# CAN.net
KiCad netlist of a schematic drawn in Altium Designer
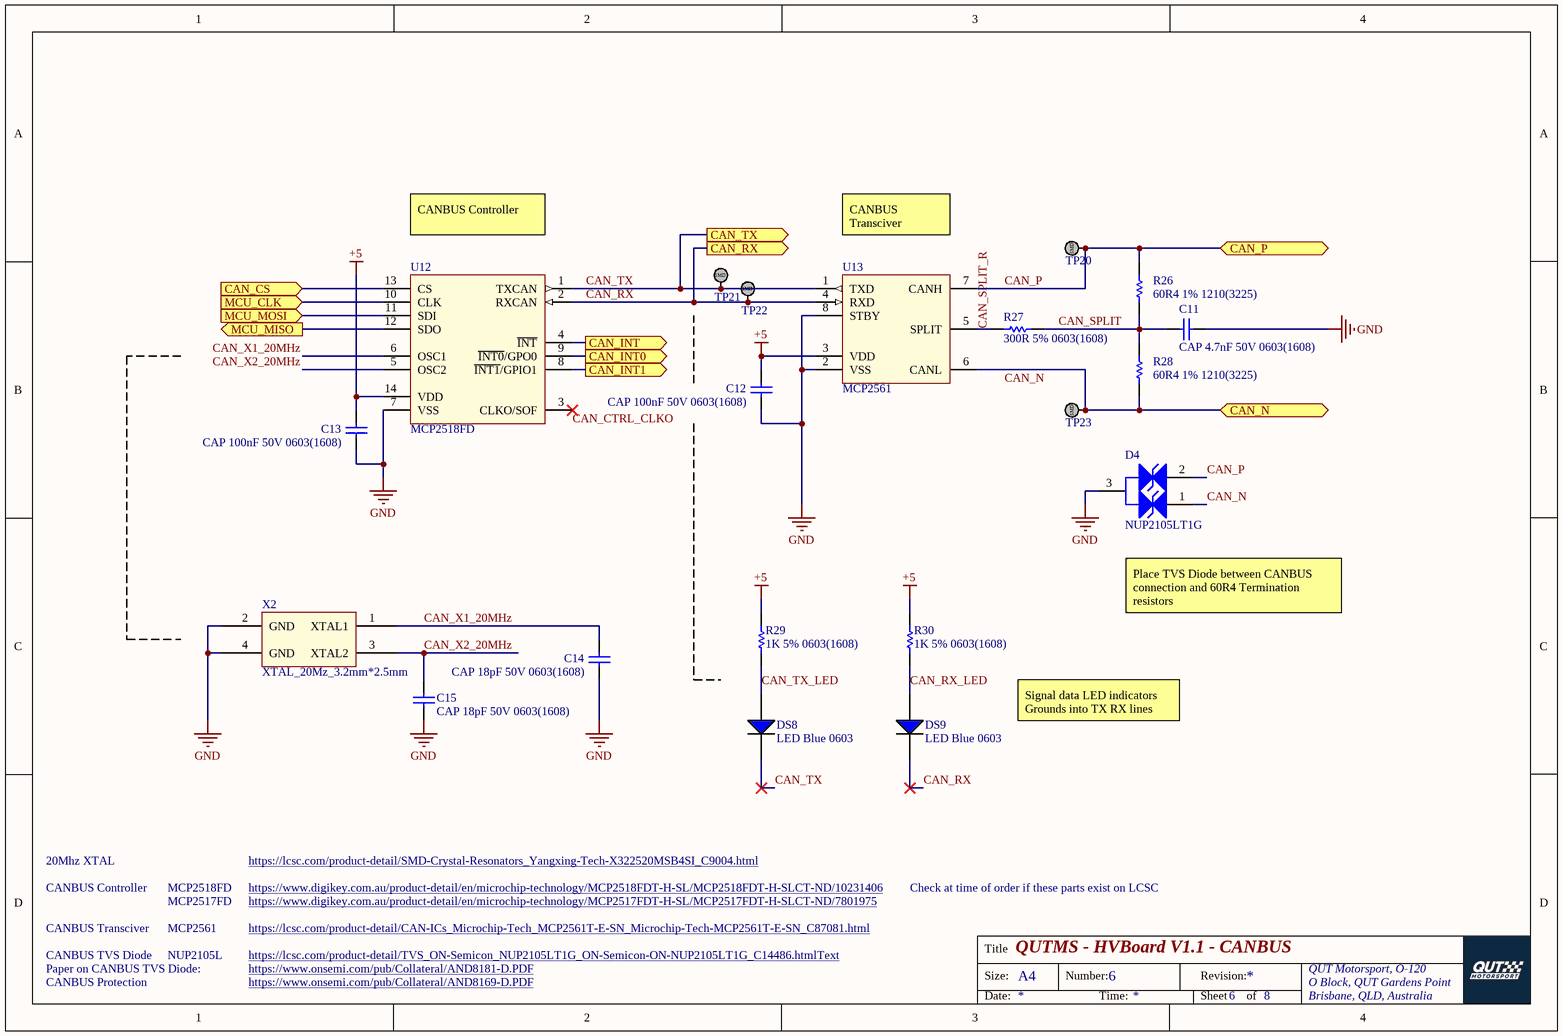
[diagram p0: CAN.SchDoc]

(export (version "E")
  (design (tool "Eeschema 10.0.6"))
  (components
    (comp (ref "C11")
      (value "CAP 4.7nF 50V 0603(1608)")
      (footprint "CAPC0603(1608)100_M")
      (description "CAP 4.7nF 50V ±5% 0603 (1608 Metric) Thickness 1mm SMD")
      (fields (field (name "TOLERANCE") "Â±5%"))
      (libsource (lib "Altium Content Vault") (part "CAP"))
    )
    (comp (ref "C12")
      (value "CAP 100nF 50V 0603(1608)")
      (footprint "CAPC0603(1608)100_L")
      (description "CAP 100nF 50V ±5% 0603 (1608 Metric) Thickness 1mm SMD")
      (fields (field (name "TOLERANCE") "Â±5%"))
      (libsource (lib "Altium Content Vault") (part "CAP"))
    )
    (comp (ref "C13")
      (value "CAP 100nF 50V 0603(1608)")
      (footprint "CAPC0603(1608)100_L")
      (description "CAP 100nF 50V ±5% 0603 (1608 Metric) Thickness 1mm SMD")
      (fields (field (name "TOLERANCE") "Â±5%"))
      (libsource (lib "Altium Content Vault") (part "CAP"))
    )
    (comp (ref "C14")
      (value "CAP 18pF 50V 0603(1608)")
      (footprint "CAPC0603(1608)100_L")
      (description "CAP 18pF 50V ±1% 0603 (1608 Metric) Thickness 1mm SMD")
      (fields (field (name "TOLERANCE") "Â±1%"))
      (libsource (lib "Altium Content Vault") (part "CAP"))
    )
    (comp (ref "C15")
      (value "CAP 18pF 50V 0603(1608)")
      (footprint "CAPC0603(1608)100_L")
      (description "CAP 18pF 50V ±1% 0603 (1608 Metric) Thickness 1mm SMD")
      (fields (field (name "TOLERANCE") "Â±1%"))
      (libsource (lib "Altium Content Vault") (part "CAP"))
    )
    (comp (ref "D4")
      (value "NUP2105LT1G")
      (footprint "ONSC-SOT-23-3-318-08_V")
      (description "Dual Line CAN Bus Protector, 3-Pin SOT-23, Pb-Free, Tape and Reel")
      (fields (field (name "MANUFACTURER") "On Semiconductor"))
      (libsource (lib "Altium Content Vault") (part "ONSC-NUP21X5X-SOT-23-3-318-08"))
    )
    (comp (ref "DS8")
      (value "LED Blue 0603")
      (footprint "LED BLUE 0603")
      (libsource (lib "QUTMS_LEDLibrary") (part "LED BLUE 0603"))
    )
    (comp (ref "DS9")
      (value "LED Blue 0603")
      (footprint "LED BLUE 0603")
      (libsource (lib "QUTMS_LEDLibrary") (part "LED BLUE 0603"))
    )
    (comp (ref "R26")
      (value "60R4 1% 1210(3225)")
      (footprint "RESC1210(3225)_L")
      (description "60R4 0.5W 1% 1210 (3225 Metric)  SMD")
      (fields (field (name "TOLERANCE") "1 %") (field (name "POWER") "0.5 W"))
      (libsource (lib "Altium Content Vault") (part "RES"))
    )
    (comp (ref "R27")
      (value "300R 5% 0603(1608)")
      (footprint "RESC0603(1608)_N")
      (description "300R 0.1W 5% 0603 (1608 Metric)  SMD")
      (fields (field (name "TOLERANCE") "5 %") (field (name "POWER") "0.1 W"))
      (libsource (lib "Altium Content Vault") (part "RES"))
    )
    (comp (ref "R28")
      (value "60R4 1% 1210(3225)")
      (footprint "RESC1210(3225)_L")
      (description "60R4 0.5W 1% 1210 (3225 Metric)  SMD")
      (fields (field (name "TOLERANCE") "1 %") (field (name "POWER") "0.5 W"))
      (libsource (lib "Altium Content Vault") (part "RES"))
    )
    (comp (ref "R29")
      (value "1K 5% 0603(1608)")
      (footprint "RESC0603(1608)_L")
      (description "1K 0.1W 5% 0603 (1608 Metric)  SMD")
      (fields (field (name "TOLERANCE") "5 %") (field (name "POWER") "0.1 W"))
      (libsource (lib "Altium Content Vault") (part "RES"))
    )
    (comp (ref "R30")
      (value "1K 5% 0603(1608)")
      (footprint "RESC0603(1608)_L")
      (description "1K 0.1W 5% 0603 (1608 Metric)  SMD")
      (fields (field (name "TOLERANCE") "5 %") (field (name "POWER") "0.1 W"))
      (libsource (lib "Altium Content Vault") (part "RES"))
    )
    (comp (ref "TP20")
      (value "TestPoint_SMD")
      (footprint "TestPointSMD")
      (libsource (lib "StandardTest") (part "TestPoint_SMD"))
    )
    (comp (ref "TP21")
      (value "TestPoint_SMD")
      (footprint "TestPointSMD")
      (libsource (lib "StandardTest") (part "TestPoint_SMD"))
    )
    (comp (ref "TP22")
      (value "TestPoint_SMD")
      (footprint "TestPointSMD")
      (libsource (lib "StandardTest") (part "TestPoint_SMD"))
    )
    (comp (ref "TP23")
      (value "TestPoint_SMD")
      (footprint "TestPointSMD")
      (libsource (lib "StandardTest") (part "TestPoint_SMD"))
    )
    (comp (ref "U12")
      (value "MCP2518FD")
      (footprint "MCP2517FD SOIC")
      (libsource (lib "QUTMS_CANLibrary") (part "MCP2518FD"))
    )
    (comp (ref "U13")
      (value "MCP2561")
      (footprint "MCP2561 SOIC")
      (libsource (lib "QUTMS_CANLibrary") (part "MCP2561"))
    )
    (comp (ref "X2")
      (value "XTAL_20Mz_3.2mm*2.5mm")
      (footprint "3.2mm*2.5mm")
      (libsource (lib "QUTMS_CrystalLibrary") (part "XTAL_20Mz_3.2mm*2.5mm"))
    )
  )
  (nets
    (net (code "1") (name "+5") (class "Default")
      (node (ref "C12") (pin "2") (pinfunction "2_2") (pintype "passive"))
      (node (ref "C13") (pin "2") (pinfunction "2_2") (pintype "passive"))
      (node (ref "R29") (pin "2") (pinfunction "2_2") (pintype "passive"))
      (node (ref "R30") (pin "2") (pinfunction "2_2") (pintype "passive"))
      (node (ref "U12") (pin "14") (pinfunction "VDD_14") (pintype "passive"))
      (node (ref "U13") (pin "3") (pinfunction "VDD_3") (pintype "passive"))
    )
    (net (code "2") (name "/CAN_CS") (class "Default")
      (node (ref "U12") (pin "13") (pinfunction "CS_13") (pintype "passive"))
    )
    (net (code "3") (name "/CAN_CTRL_CLKO") (class "Default")
      (node (ref "U12") (pin "3") (pinfunction "CLKO/SOF_3") (pintype "passive+no_connect"))
    )
    (net (code "4") (name "/CAN_INT") (class "Default")
      (node (ref "U12") (pin "4") (pinfunction "~{INT}_4") (pintype "passive"))
    )
    (net (code "5") (name "/CAN_INT0") (class "Default")
      (node (ref "U12") (pin "9") (pinfunction "~{INT0}/GPO0_9") (pintype "passive"))
    )
    (net (code "6") (name "/CAN_INT1") (class "Default")
      (node (ref "U12") (pin "8") (pinfunction "~{INT1}/GPIO1_8") (pintype "passive"))
    )
    (net (code "7") (name "/CAN_N") (class "Default")
      (node (ref "D4") (pin "1") (pinfunction "K_1") (pintype "passive"))
      (node (ref "R28") (pin "1") (pinfunction "1_1") (pintype "passive"))
      (node (ref "TP23") (pin "1") (pinfunction "1_1") (pintype "passive"))
      (node (ref "U13") (pin "6") (pinfunction "CANL_6") (pintype "passive"))
    )
    (net (code "8") (name "/CAN_P") (class "Default")
      (node (ref "D4") (pin "2") (pinfunction "K_2") (pintype "passive"))
      (node (ref "R26") (pin "2") (pinfunction "2_2") (pintype "passive"))
      (node (ref "TP20") (pin "1") (pinfunction "1_1") (pintype "passive"))
      (node (ref "U13") (pin "7") (pinfunction "CANH_7") (pintype "passive"))
    )
    (net (code "9") (name "/CAN_RX") (class "Default")
      (node (ref "DS9") (pin "2") (pinfunction "C_2") (pintype "passive"))
      (node (ref "TP22") (pin "1") (pinfunction "1_1") (pintype "passive"))
      (node (ref "U12") (pin "2") (pinfunction "RXCAN_2") (pintype "input"))
      (node (ref "U13") (pin "4") (pinfunction "RXD_4") (pintype "input"))
    )
    (net (code "10") (name "/CAN_RX_LED") (class "Default")
      (node (ref "DS9") (pin "1") (pinfunction "A_1") (pintype "passive"))
      (node (ref "R30") (pin "1") (pinfunction "1_1") (pintype "passive"))
    )
    (net (code "11") (name "/CAN_SPLIT") (class "Default")
      (node (ref "C11") (pin "2") (pinfunction "2_2") (pintype "passive"))
      (node (ref "R26") (pin "1") (pinfunction "1_1") (pintype "passive"))
      (node (ref "R27") (pin "2") (pinfunction "2_2") (pintype "passive"))
      (node (ref "R28") (pin "2") (pinfunction "2_2") (pintype "passive"))
    )
    (net (code "12") (name "/CAN_SPLIT_R") (class "Default")
      (node (ref "R27") (pin "1") (pinfunction "1_1") (pintype "passive"))
      (node (ref "U13") (pin "5") (pinfunction "SPLIT_5") (pintype "passive"))
    )
    (net (code "13") (name "/CAN_TX") (class "Default")
      (node (ref "DS8") (pin "2") (pinfunction "C_2") (pintype "passive"))
      (node (ref "TP21") (pin "1") (pinfunction "1_1") (pintype "passive"))
      (node (ref "U12") (pin "1") (pinfunction "TXCAN_1") (pintype "output"))
      (node (ref "U13") (pin "1") (pinfunction "TXD_1") (pintype "output"))
    )
    (net (code "14") (name "/CAN_TX_LED") (class "Default")
      (node (ref "DS8") (pin "1") (pinfunction "A_1") (pintype "passive"))
      (node (ref "R29") (pin "1") (pinfunction "1_1") (pintype "passive"))
    )
    (net (code "15") (name "/CAN_X1_20MHz") (class "Default")
      (node (ref "C14") (pin "2") (pinfunction "2_2") (pintype "passive"))
      (node (ref "U12") (pin "6") (pinfunction "OSC1_6") (pintype "passive"))
      (node (ref "X2") (pin "1") (pinfunction "XTAL1_1") (pintype "passive"))
    )
    (net (code "16") (name "/CAN_X2_20MHz") (class "Default")
      (node (ref "C15") (pin "2") (pinfunction "2_2") (pintype "passive"))
      (node (ref "U12") (pin "5") (pinfunction "OSC2_5") (pintype "passive"))
      (node (ref "X2") (pin "3") (pinfunction "XTAL2_3") (pintype "passive"))
    )
    (net (code "17") (name "/MCU_CLK") (class "Default")
      (node (ref "U12") (pin "10") (pinfunction "CLK_10") (pintype "passive"))
    )
    (net (code "18") (name "/MCU_MISO") (class "Default")
      (node (ref "U12") (pin "12") (pinfunction "SDO_12") (pintype "passive"))
    )
    (net (code "19") (name "/MCU_MOSI") (class "Default")
      (node (ref "U12") (pin "11") (pinfunction "SDI_11") (pintype "passive"))
    )
    (net (code "20") (name "GND") (class "Default")
      (node (ref "C11") (pin "1") (pinfunction "1_1") (pintype "passive"))
      (node (ref "C12") (pin "1") (pinfunction "1_1") (pintype "passive"))
      (node (ref "C13") (pin "1") (pinfunction "1_1") (pintype "passive"))
      (node (ref "C14") (pin "1") (pinfunction "1_1") (pintype "passive"))
      (node (ref "C15") (pin "1") (pinfunction "1_1") (pintype "passive"))
      (node (ref "D4") (pin "3") (pinfunction "K_3") (pintype "passive"))
      (node (ref "U12") (pin "7") (pinfunction "VSS_7") (pintype "passive"))
      (node (ref "U13") (pin "2") (pinfunction "VSS_2") (pintype "passive"))
      (node (ref "U13") (pin "8") (pinfunction "STBY_8") (pintype "passive"))
      (node (ref "X2") (pin "2") (pinfunction "GND_2") (pintype "passive"))
      (node (ref "X2") (pin "4") (pinfunction "GND_4") (pintype "passive"))
    )
  )
)
